# vps-r2_0-20-with-description.net
KiCad netlist of a schematic drawn in EAGLE
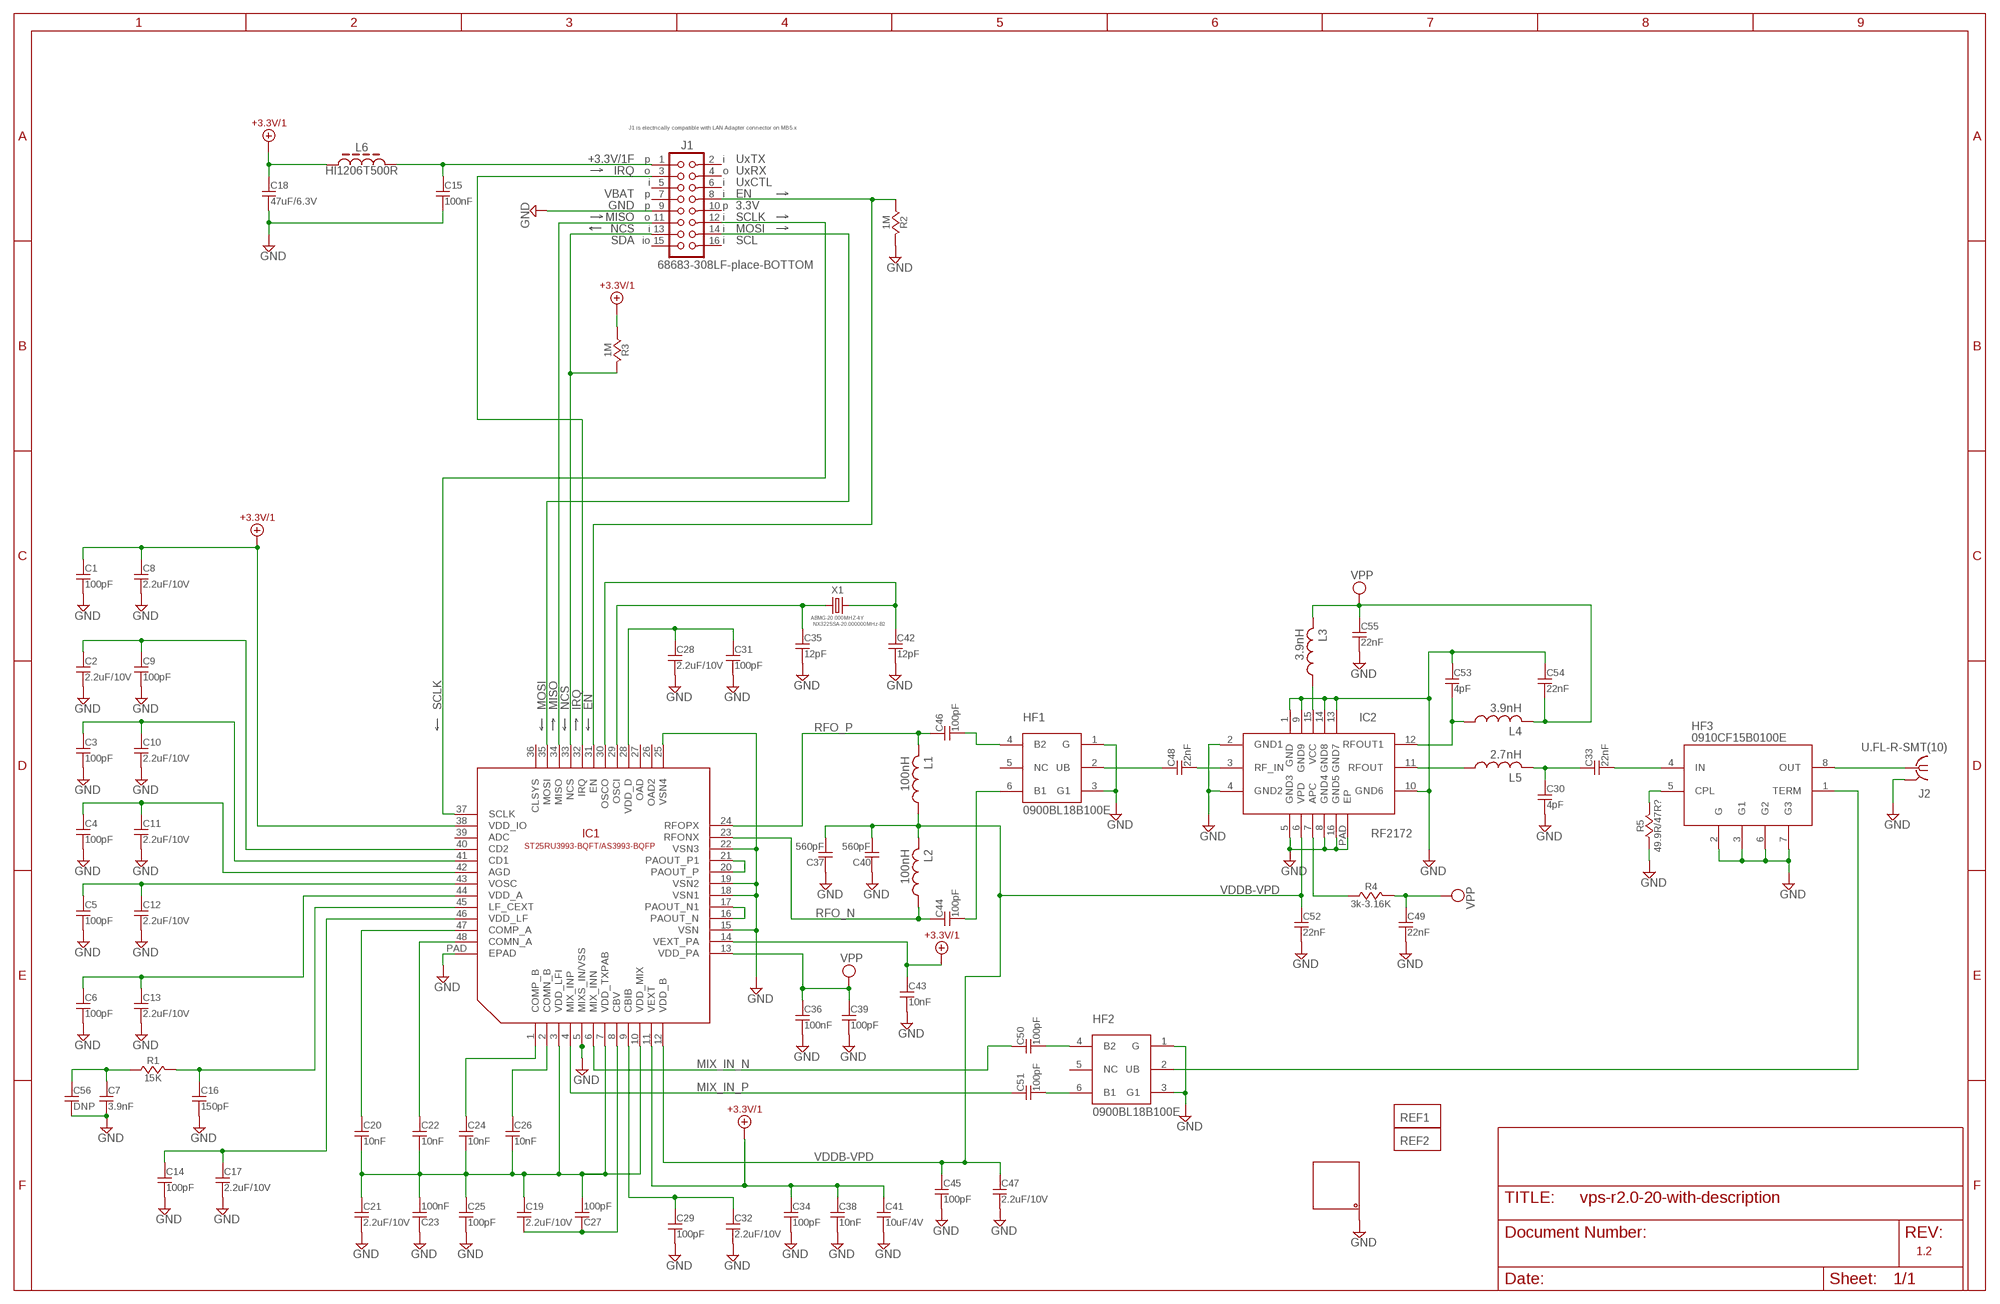
[diagram p0: schematic, sheet 1]

(export (version "E")
  (design (tool "Eeschema 10.0.6"))
  (components
    (comp (ref "C1")
      (value "100pF")
      (footprint "eagle-import:0603")
      (libsource (lib "eagle-import") (part "C-0603"))
    )
    (comp (ref "C2")
      (value "2.2uF/10V")
      (footprint "eagle-import:0603")
      (libsource (lib "eagle-import") (part "C-0603"))
    )
    (comp (ref "C3")
      (value "100pF")
      (footprint "eagle-import:0603")
      (libsource (lib "eagle-import") (part "C-0603"))
    )
    (comp (ref "C4")
      (value "100pF")
      (footprint "eagle-import:0603")
      (libsource (lib "eagle-import") (part "C-0603"))
    )
    (comp (ref "C5")
      (value "100pF")
      (footprint "eagle-import:0603")
      (libsource (lib "eagle-import") (part "C-0603"))
    )
    (comp (ref "C6")
      (value "100pF")
      (footprint "eagle-import:0603")
      (libsource (lib "eagle-import") (part "C-0603"))
    )
    (comp (ref "C7")
      (value "3.9nF")
      (footprint "eagle-import:0603")
      (libsource (lib "eagle-import") (part "C-0603"))
    )
    (comp (ref "C8")
      (value "2.2uF/10V")
      (footprint "eagle-import:0603")
      (libsource (lib "eagle-import") (part "C-0603"))
    )
    (comp (ref "C9")
      (value "100pF")
      (footprint "eagle-import:0603")
      (libsource (lib "eagle-import") (part "C-0603"))
    )
    (comp (ref "C10")
      (value "2.2uF/10V")
      (footprint "eagle-import:0603")
      (libsource (lib "eagle-import") (part "C-0603"))
    )
    (comp (ref "C11")
      (value "2.2uF/10V")
      (footprint "eagle-import:0603")
      (libsource (lib "eagle-import") (part "C-0603"))
    )
    (comp (ref "C12")
      (value "2.2uF/10V")
      (footprint "eagle-import:0603")
      (libsource (lib "eagle-import") (part "C-0603"))
    )
    (comp (ref "C13")
      (value "2.2uF/10V")
      (footprint "eagle-import:0603")
      (libsource (lib "eagle-import") (part "C-0603"))
    )
    (comp (ref "C14")
      (value "100pF")
      (footprint "eagle-import:0603")
      (libsource (lib "eagle-import") (part "C-0603"))
    )
    (comp (ref "C15")
      (value "100nF")
      (footprint "eagle-import:0603")
      (libsource (lib "eagle-import") (part "C-0603"))
    )
    (comp (ref "C16")
      (value "150pF")
      (footprint "eagle-import:0603")
      (libsource (lib "eagle-import") (part "C-0603"))
    )
    (comp (ref "C17")
      (value "2.2uF/10V")
      (footprint "eagle-import:0603")
      (libsource (lib "eagle-import") (part "C-0603"))
    )
    (comp (ref "C18")
      (value "47uF/6.3V")
      (footprint "eagle-import:1206")
      (libsource (lib "eagle-import") (part "C-1206"))
    )
    (comp (ref "C19")
      (value "2.2uF/10V")
      (footprint "eagle-import:0603")
      (libsource (lib "eagle-import") (part "C-0603"))
    )
    (comp (ref "C20")
      (value "10nF")
      (footprint "eagle-import:0603")
      (libsource (lib "eagle-import") (part "C-0603"))
    )
    (comp (ref "C21")
      (value "2.2uF/10V")
      (footprint "eagle-import:0603")
      (libsource (lib "eagle-import") (part "C-0603"))
    )
    (comp (ref "C22")
      (value "10nF")
      (footprint "eagle-import:0603")
      (libsource (lib "eagle-import") (part "C-0603"))
    )
    (comp (ref "C23")
      (value "100nF")
      (footprint "eagle-import:0603")
      (libsource (lib "eagle-import") (part "C-0603"))
    )
    (comp (ref "C24")
      (value "10nF")
      (footprint "eagle-import:0603")
      (libsource (lib "eagle-import") (part "C-0603"))
    )
    (comp (ref "C25")
      (value "100pF")
      (footprint "eagle-import:0603")
      (libsource (lib "eagle-import") (part "C-0603"))
    )
    (comp (ref "C26")
      (value "10nF")
      (footprint "eagle-import:0603")
      (libsource (lib "eagle-import") (part "C-0603"))
    )
    (comp (ref "C27")
      (value "100pF")
      (footprint "eagle-import:0603")
      (libsource (lib "eagle-import") (part "C-0603"))
    )
    (comp (ref "C28")
      (value "2.2uF/10V")
      (footprint "eagle-import:0603")
      (libsource (lib "eagle-import") (part "C-0603"))
    )
    (comp (ref "C29")
      (value "100pF")
      (footprint "eagle-import:0603")
      (libsource (lib "eagle-import") (part "C-0603"))
    )
    (comp (ref "C30")
      (value "4pF")
      (footprint "eagle-import:0603")
      (libsource (lib "eagle-import") (part "C-0603"))
    )
    (comp (ref "C31")
      (value "100pF")
      (footprint "eagle-import:0603")
      (libsource (lib "eagle-import") (part "C-0603"))
    )
    (comp (ref "C32")
      (value "2.2uF/10V")
      (footprint "eagle-import:0603")
      (libsource (lib "eagle-import") (part "C-0603"))
    )
    (comp (ref "C33")
      (value "22nF")
      (footprint "eagle-import:0603")
      (libsource (lib "eagle-import") (part "C-0603"))
    )
    (comp (ref "C34")
      (value "100pF")
      (footprint "eagle-import:0603")
      (libsource (lib "eagle-import") (part "C-0603"))
    )
    (comp (ref "C35")
      (value "12pF")
      (footprint "eagle-import:0603")
      (libsource (lib "eagle-import") (part "C-0603"))
    )
    (comp (ref "C36")
      (value "100nF")
      (footprint "eagle-import:0603")
      (libsource (lib "eagle-import") (part "C-0603"))
    )
    (comp (ref "C37")
      (value "560pF")
      (footprint "eagle-import:0603")
      (libsource (lib "eagle-import") (part "C-0603"))
    )
    (comp (ref "C38")
      (value "10nF")
      (footprint "eagle-import:0603")
      (libsource (lib "eagle-import") (part "C-0603"))
    )
    (comp (ref "C39")
      (value "100pF")
      (footprint "eagle-import:0603")
      (libsource (lib "eagle-import") (part "C-0603"))
    )
    (comp (ref "C40")
      (value "560pF")
      (footprint "eagle-import:0603")
      (libsource (lib "eagle-import") (part "C-0603"))
    )
    (comp (ref "C41")
      (value "10uF/4V")
      (footprint "eagle-import:0603")
      (libsource (lib "eagle-import") (part "C-0603"))
    )
    (comp (ref "C42")
      (value "12pF")
      (footprint "eagle-import:0603")
      (libsource (lib "eagle-import") (part "C-0603"))
    )
    (comp (ref "C43")
      (value "10nF")
      (footprint "eagle-import:0603")
      (libsource (lib "eagle-import") (part "C-0603"))
    )
    (comp (ref "C44")
      (value "100pF")
      (footprint "eagle-import:0603")
      (libsource (lib "eagle-import") (part "C-0603"))
    )
    (comp (ref "C45")
      (value "100pF")
      (footprint "eagle-import:0603")
      (libsource (lib "eagle-import") (part "C-0603"))
    )
    (comp (ref "C46")
      (value "100pF")
      (footprint "eagle-import:0603")
      (libsource (lib "eagle-import") (part "C-0603"))
    )
    (comp (ref "C47")
      (value "2.2uF/10V")
      (footprint "eagle-import:0603")
      (libsource (lib "eagle-import") (part "C-0603"))
    )
    (comp (ref "C48")
      (value "22nF")
      (footprint "eagle-import:0603")
      (libsource (lib "eagle-import") (part "C-0603"))
    )
    (comp (ref "C49")
      (value "22nF")
      (footprint "eagle-import:0603")
      (libsource (lib "eagle-import") (part "C-0603"))
    )
    (comp (ref "C50")
      (value "100pF")
      (footprint "eagle-import:0603")
      (libsource (lib "eagle-import") (part "C-0603"))
    )
    (comp (ref "C51")
      (value "100pF")
      (footprint "eagle-import:0603")
      (libsource (lib "eagle-import") (part "C-0603"))
    )
    (comp (ref "C52")
      (value "22nF")
      (footprint "eagle-import:0603")
      (libsource (lib "eagle-import") (part "C-0603"))
    )
    (comp (ref "C53")
      (value "4pF")
      (footprint "eagle-import:0603")
      (libsource (lib "eagle-import") (part "C-0603"))
    )
    (comp (ref "C54")
      (value "22nF")
      (footprint "eagle-import:0603")
      (libsource (lib "eagle-import") (part "C-0603"))
    )
    (comp (ref "C55")
      (value "22nF")
      (footprint "eagle-import:0603")
      (libsource (lib "eagle-import") (part "C-0603"))
    )
    (comp (ref "C56")
      (value "DNP")
      (footprint "eagle-import:0603")
      (libsource (lib "eagle-import") (part "C-0603"))
    )
    (comp (ref "HF1")
      (value "0900BL18B100E")
      (footprint "eagle-import:JTIBALUN")
      (fields (field (name "MF") "JOHANSON TECHNOLIGIES"))
      (libsource (lib "eagle-import") (part "JTI_BALUN"))
    )
    (comp (ref "HF2")
      (value "0900BL18B100E")
      (footprint "eagle-import:JTIBALUN")
      (fields (field (name "MF") "JOHANSON TECHNOLIGIES"))
      (libsource (lib "eagle-import") (part "JTI_BALUN"))
    )
    (comp (ref "HF3")
      (value "0910CF15B0100E")
      (footprint "eagle-import:JTICPL")
      (libsource (lib "eagle-import") (part "JTI_CLP_FIL"))
    )
    (comp (ref "IC1")
      (value "ST25RU3993-BQFT/AS3993-BQFP")
      (footprint "eagle-import:LFCSP_7X7_48")
      (libsource (lib "eagle-import") (part "AS3993-BQFP"))
    )
    (comp (ref "IC2")
      (value "RF2172")
      (footprint "eagle-import:QFN164X4")
      (libsource (lib "eagle-import") (part "RF2172"))
    )
    (comp (ref "J1")
      (value "68683-308LF-place-BOTTOM")
      (footprint "eagle-import:MA08-2")
      (libsource (lib "eagle-import") (part "MA08-2"))
    )
    (comp (ref "J2")
      (value "U.FL-R-SMT(10)")
      (footprint "eagle-import:MC-921")
      (libsource (lib "eagle-import") (part "MC-921"))
    )
    (comp (ref "L1")
      (value "100nH")
      (footprint "eagle-import:L0603")
      (libsource (lib "eagle-import") (part "L0603"))
    )
    (comp (ref "L2")
      (value "100nH")
      (footprint "eagle-import:L0603")
      (libsource (lib "eagle-import") (part "L0603"))
    )
    (comp (ref "L3")
      (value "3.9nH")
      (footprint "eagle-import:L0603")
      (libsource (lib "eagle-import") (part "L0603"))
    )
    (comp (ref "L4")
      (value "3.9nH")
      (footprint "eagle-import:L0603")
      (libsource (lib "eagle-import") (part "L0603"))
    )
    (comp (ref "L5")
      (value "2.7nH")
      (footprint "eagle-import:L0603")
      (libsource (lib "eagle-import") (part "L0603"))
    )
    (comp (ref "L6")
      (value "HI1206T500R")
      (footprint "eagle-import:1206")
      (libsource (lib "eagle-import") (part "L-1206"))
    )
    (comp (ref "PCB1")
      (value "PCB-VPS-1")
      (footprint "eagle-import:PCB-VPS")
      (libsource (lib "eagle-import") (part "PCB-VPS-1"))
    )
    (comp (ref "R1")
      (value "15K")
      (footprint "eagle-import:0603")
      (libsource (lib "eagle-import") (part "R-0603"))
    )
    (comp (ref "R2")
      (value "1M")
      (footprint "eagle-import:0603")
      (libsource (lib "eagle-import") (part "R-0603"))
    )
    (comp (ref "R3")
      (value "1M")
      (footprint "eagle-import:0603")
      (libsource (lib "eagle-import") (part "R-0603"))
    )
    (comp (ref "R4")
      (value "3k-3.16K")
      (footprint "eagle-import:0603")
      (libsource (lib "eagle-import") (part "R-0603"))
    )
    (comp (ref "R5")
      (value "49.9R/47R?")
      (footprint "eagle-import:0603")
      (libsource (lib "eagle-import") (part "R-0603"))
    )
    (comp (ref "REF1")
      (value "REF")
      (footprint "eagle-import:REF")
      (libsource (lib "eagle-import") (part "REF"))
    )
    (comp (ref "REF2")
      (value "REF")
      (footprint "eagle-import:REF")
      (libsource (lib "eagle-import") (part "REF"))
    )
    (comp (ref "X1")
      (value "ABMG-20.000MHZ-4Y")
      (footprint "eagle-import:7M")
      (libsource (lib "eagle-import") (part "XTAL-7M"))
    )
  )
  (nets
    (net (code "1") (name "+3.3V{slash}1") (class "Default")
      (node (ref "C1") (pin "1") (pinfunction "1_1") (pintype "passive"))
      (node (ref "C18") (pin "1") (pinfunction "1_1") (pintype "passive"))
      (node (ref "C34") (pin "1") (pinfunction "1_1") (pintype "passive"))
      (node (ref "C38") (pin "1") (pinfunction "1_1") (pintype "passive"))
      (node (ref "C41") (pin "1") (pinfunction "1_1") (pintype "passive"))
      (node (ref "C43") (pin "1") (pinfunction "1_1") (pintype "passive"))
      (node (ref "C8") (pin "1") (pinfunction "1_1") (pintype "passive"))
      (node (ref "IC1") (pin "11") (pinfunction "VEXT_11") (pintype "bidirectional"))
      (node (ref "IC1") (pin "14") (pinfunction "VEXT_PA_14") (pintype "bidirectional"))
      (node (ref "IC1") (pin "38") (pinfunction "VDD_IO_38") (pintype "bidirectional"))
      (node (ref "L6") (pin "1") (pinfunction "1_1") (pintype "passive"))
      (node (ref "R3") (pin "1") (pinfunction "1_1") (pintype "passive"))
    )
    (net (code "2") (name "/+3.3V{slash}1F") (class "Default")
      (node (ref "C15") (pin "1") (pinfunction "1_1") (pintype "passive"))
      (node (ref "J1") (pin "1") (pinfunction "1_1") (pintype "passive"))
      (node (ref "L6") (pin "2") (pinfunction "2_2") (pintype "passive"))
    )
    (net (code "3") (name "/EN") (class "Default")
      (node (ref "IC1") (pin "31") (pinfunction "EN_31") (pintype "bidirectional"))
      (node (ref "J1") (pin "8") (pinfunction "8_8") (pintype "passive"))
      (node (ref "R2") (pin "1") (pinfunction "1_1") (pintype "passive"))
    )
    (net (code "4") (name "/IRQ") (class "Default")
      (node (ref "IC1") (pin "32") (pinfunction "IRQ_32") (pintype "bidirectional"))
      (node (ref "J1") (pin "3") (pinfunction "3_3") (pintype "passive"))
    )
    (net (code "5") (name "/MISO") (class "Default")
      (node (ref "IC1") (pin "34") (pinfunction "MISO_34") (pintype "bidirectional"))
      (node (ref "J1") (pin "11") (pinfunction "11_11") (pintype "passive"))
    )
    (net (code "6") (name "/MIX_IN_N") (class "Default")
      (node (ref "C50") (pin "1") (pinfunction "1_1") (pintype "passive"))
      (node (ref "IC1") (pin "6") (pinfunction "MIX_INN_6") (pintype "bidirectional"))
    )
    (net (code "7") (name "/MIX_IN_P") (class "Default")
      (node (ref "C51") (pin "1") (pinfunction "1_1") (pintype "passive"))
      (node (ref "IC1") (pin "4") (pinfunction "MIX_INP_4") (pintype "bidirectional"))
    )
    (net (code "8") (name "/MOSI") (class "Default")
      (node (ref "IC1") (pin "35") (pinfunction "MOSI_35") (pintype "bidirectional"))
      (node (ref "J1") (pin "14") (pinfunction "14_14") (pintype "passive"))
    )
    (net (code "9") (name "/NCS") (class "Default")
      (node (ref "IC1") (pin "33") (pinfunction "NCS_33") (pintype "bidirectional"))
      (node (ref "J1") (pin "13") (pinfunction "13_13") (pintype "passive"))
      (node (ref "R3") (pin "2") (pinfunction "2_2") (pintype "passive"))
    )
    (net (code "10") (name "/RFO_N") (class "Default")
      (node (ref "C44") (pin "1") (pinfunction "1_1") (pintype "passive"))
      (node (ref "IC1") (pin "23") (pinfunction "RFONX_23") (pintype "bidirectional"))
      (node (ref "L2") (pin "1") (pinfunction "1_1") (pintype "passive"))
    )
    (net (code "11") (name "/RFO_P") (class "Default")
      (node (ref "C46") (pin "1") (pinfunction "1_1") (pintype "passive"))
      (node (ref "IC1") (pin "24") (pinfunction "RFOPX_24") (pintype "bidirectional"))
      (node (ref "L1") (pin "2") (pinfunction "2_2") (pintype "passive"))
    )
    (net (code "12") (name "/SCLK") (class "Default")
      (node (ref "IC1") (pin "37") (pinfunction "SCLK_37") (pintype "bidirectional"))
      (node (ref "J1") (pin "12") (pinfunction "12_12") (pintype "passive"))
    )
    (net (code "13") (name "/VDDB-VPD") (class "Default")
      (node (ref "C37") (pin "2") (pinfunction "2_2") (pintype "passive"))
      (node (ref "C40") (pin "2") (pinfunction "2_2") (pintype "passive"))
      (node (ref "C45") (pin "1") (pinfunction "1_1") (pintype "passive"))
      (node (ref "C47") (pin "1") (pinfunction "1_1") (pintype "passive"))
      (node (ref "C52") (pin "1") (pinfunction "1_1") (pintype "passive"))
      (node (ref "IC1") (pin "12") (pinfunction "VDD_B_12") (pintype "bidirectional"))
      (node (ref "IC2") (pin "6") (pinfunction "VPD_6") (pintype "bidirectional"))
      (node (ref "L1") (pin "1") (pinfunction "1_1") (pintype "passive"))
      (node (ref "L2") (pin "2") (pinfunction "2_2") (pintype "passive"))
    )
    (net (code "14") (name "GND") (class "Default")
      (node (ref "C1") (pin "2") (pinfunction "2_2") (pintype "passive"))
      (node (ref "C10") (pin "2") (pinfunction "2_2") (pintype "passive"))
      (node (ref "C11") (pin "2") (pinfunction "2_2") (pintype "passive"))
      (node (ref "C12") (pin "2") (pinfunction "2_2") (pintype "passive"))
      (node (ref "C13") (pin "2") (pinfunction "2_2") (pintype "passive"))
      (node (ref "C14") (pin "2") (pinfunction "2_2") (pintype "passive"))
      (node (ref "C15") (pin "2") (pinfunction "2_2") (pintype "passive"))
      (node (ref "C16") (pin "2") (pinfunction "2_2") (pintype "passive"))
      (node (ref "C17") (pin "2") (pinfunction "2_2") (pintype "passive"))
      (node (ref "C18") (pin "2") (pinfunction "2_2") (pintype "passive"))
      (node (ref "C2") (pin "2") (pinfunction "2_2") (pintype "passive"))
      (node (ref "C21") (pin "2") (pinfunction "2_2") (pintype "passive"))
      (node (ref "C23") (pin "1") (pinfunction "1_1") (pintype "passive"))
      (node (ref "C25") (pin "2") (pinfunction "2_2") (pintype "passive"))
      (node (ref "C28") (pin "2") (pinfunction "2_2") (pintype "passive"))
      (node (ref "C29") (pin "2") (pinfunction "2_2") (pintype "passive"))
      (node (ref "C3") (pin "2") (pinfunction "2_2") (pintype "passive"))
      (node (ref "C30") (pin "2") (pinfunction "2_2") (pintype "passive"))
      (node (ref "C31") (pin "2") (pinfunction "2_2") (pintype "passive"))
      (node (ref "C32") (pin "2") (pinfunction "2_2") (pintype "passive"))
      (node (ref "C34") (pin "2") (pinfunction "2_2") (pintype "passive"))
      (node (ref "C35") (pin "2") (pinfunction "2_2") (pintype "passive"))
      (node (ref "C36") (pin "2") (pinfunction "2_2") (pintype "passive"))
      (node (ref "C37") (pin "1") (pinfunction "1_1") (pintype "passive"))
      (node (ref "C38") (pin "2") (pinfunction "2_2") (pintype "passive"))
      (node (ref "C39") (pin "2") (pinfunction "2_2") (pintype "passive"))
      (node (ref "C4") (pin "2") (pinfunction "2_2") (pintype "passive"))
      (node (ref "C40") (pin "1") (pinfunction "1_1") (pintype "passive"))
      (node (ref "C41") (pin "2") (pinfunction "2_2") (pintype "passive"))
      (node (ref "C42") (pin "2") (pinfunction "2_2") (pintype "passive"))
      (node (ref "C43") (pin "2") (pinfunction "2_2") (pintype "passive"))
      (node (ref "C45") (pin "2") (pinfunction "2_2") (pintype "passive"))
      (node (ref "C47") (pin "2") (pinfunction "2_2") (pintype "passive"))
      (node (ref "C49") (pin "2") (pinfunction "2_2") (pintype "passive"))
      (node (ref "C5") (pin "2") (pinfunction "2_2") (pintype "passive"))
      (node (ref "C52") (pin "2") (pinfunction "2_2") (pintype "passive"))
      (node (ref "C53") (pin "1") (pinfunction "1_1") (pintype "passive"))
      (node (ref "C54") (pin "1") (pinfunction "1_1") (pintype "passive"))
      (node (ref "C55") (pin "2") (pinfunction "2_2") (pintype "passive"))
      (node (ref "C56") (pin "2") (pinfunction "2_2") (pintype "passive"))
      (node (ref "C6") (pin "2") (pinfunction "2_2") (pintype "passive"))
      (node (ref "C7") (pin "2") (pinfunction "2_2") (pintype "passive"))
      (node (ref "C8") (pin "2") (pinfunction "2_2") (pintype "passive"))
      (node (ref "C9") (pin "2") (pinfunction "2_2") (pintype "passive"))
      (node (ref "HF1") (pin "1") (pinfunction "G_1") (pintype "bidirectional"))
      (node (ref "HF1") (pin "3") (pinfunction "G1_3") (pintype "bidirectional"))
      (node (ref "HF2") (pin "1") (pinfunction "G_1") (pintype "bidirectional"))
      (node (ref "HF2") (pin "3") (pinfunction "G1_3") (pintype "bidirectional"))
      (node (ref "HF3") (pin "2") (pinfunction "G_2") (pintype "bidirectional"))
      (node (ref "HF3") (pin "3") (pinfunction "G1_3") (pintype "bidirectional"))
      (node (ref "HF3") (pin "6") (pinfunction "G2_6") (pintype "bidirectional"))
      (node (ref "HF3") (pin "7") (pinfunction "G3_7") (pintype "bidirectional"))
      (node (ref "IC1") (pin "15") (pinfunction "VSN_15") (pintype "bidirectional"))
      (node (ref "IC1") (pin "18") (pinfunction "VSN1_18") (pintype "bidirectional"))
      (node (ref "IC1") (pin "19") (pinfunction "VSN2_19") (pintype "bidirectional"))
      (node (ref "IC1") (pin "22") (pinfunction "VSN3_22") (pintype "bidirectional"))
      (node (ref "IC1") (pin "25") (pinfunction "VSN4_25") (pintype "bidirectional"))
      (node (ref "IC1") (pin "5") (pinfunction "MIXS_IN/VSS_5") (pintype "bidirectional"))
      (node (ref "IC1") (pin "PAD") (pinfunction "EPAD_PAD") (pintype "bidirectional"))
      (node (ref "IC2") (pin "1") (pinfunction "GND_1") (pintype "bidirectional"))
      (node (ref "IC2") (pin "10") (pinfunction "GND6_10") (pintype "bidirectional"))
      (node (ref "IC2") (pin "13") (pinfunction "GND7_13") (pintype "bidirectional"))
      (node (ref "IC2") (pin "14") (pinfunction "GND8_14") (pintype "bidirectional"))
      (node (ref "IC2") (pin "16") (pinfunction "GND5_16") (pintype "bidirectional"))
      (node (ref "IC2") (pin "2") (pinfunction "GND1_2") (pintype "bidirectional"))
      (node (ref "IC2") (pin "4") (pinfunction "GND2_4") (pintype "bidirectional"))
      (node (ref "IC2") (pin "5") (pinfunction "GND3_5") (pintype "bidirectional"))
      (node (ref "IC2") (pin "8") (pinfunction "GND4_8") (pintype "bidirectional"))
      (node (ref "IC2") (pin "9") (pinfunction "GND9_9") (pintype "bidirectional"))
      (node (ref "IC2") (pin "PAD") (pinfunction "EP_PAD") (pintype "bidirectional"))
      (node (ref "J1") (pin "9") (pinfunction "9_9") (pintype "passive"))
      (node (ref "J2") (pin "2@1") (pinfunction "GND_2@1") (pintype "passive"))
      (node (ref "J2") (pin "2@2") (pinfunction "GND_2@2") (pintype "passive"))
      (node (ref "PCB1") (pin "VPS_PCB_1") (pinfunction "VPS_PCB_1_VPS_PCB_1") (pintype "bidirectional"))
      (node (ref "R2") (pin "2") (pinfunction "2_2") (pintype "passive"))
      (node (ref "R5") (pin "1") (pinfunction "1_1") (pintype "passive"))
    )
    (net (code "15") (name "Net-(C30-Pad1)") (class "Default")
      (node (ref "C30") (pin "1") (pinfunction "1_1") (pintype "passive"))
      (node (ref "C33") (pin "1") (pinfunction "1_1") (pintype "passive"))
      (node (ref "L5") (pin "2") (pinfunction "2_2") (pintype "passive"))
    )
    (net (code "16") (name "Net-(C56-Pad1)") (class "Default")
      (node (ref "C56") (pin "1") (pinfunction "1_1") (pintype "passive"))
      (node (ref "C7") (pin "1") (pinfunction "1_1") (pintype "passive"))
      (node (ref "R1") (pin "1") (pinfunction "1_1") (pintype "passive"))
    )
    (net (code "17") (name "Net-(HF1-B1)") (class "Default")
      (node (ref "C44") (pin "2") (pinfunction "2_2") (pintype "passive"))
      (node (ref "HF1") (pin "6") (pinfunction "B1_6") (pintype "bidirectional"))
    )
    (net (code "18") (name "Net-(HF1-B2)") (class "Default")
      (node (ref "C46") (pin "2") (pinfunction "2_2") (pintype "passive"))
      (node (ref "HF1") (pin "4") (pinfunction "B2_4") (pintype "bidirectional"))
    )
    (net (code "19") (name "Net-(HF1-UB)") (class "Default")
      (node (ref "C48") (pin "1") (pinfunction "1_1") (pintype "passive"))
      (node (ref "HF1") (pin "2") (pinfunction "UB_2") (pintype "bidirectional"))
    )
    (net (code "20") (name "Net-(HF2-B1)") (class "Default")
      (node (ref "C51") (pin "2") (pinfunction "2_2") (pintype "passive"))
      (node (ref "HF2") (pin "6") (pinfunction "B1_6") (pintype "bidirectional"))
    )
    (net (code "21") (name "Net-(HF2-B2)") (class "Default")
      (node (ref "C50") (pin "2") (pinfunction "2_2") (pintype "passive"))
      (node (ref "HF2") (pin "4") (pinfunction "B2_4") (pintype "bidirectional"))
    )
    (net (code "22") (name "Net-(HF2-UB)") (class "Default")
      (node (ref "HF2") (pin "2") (pinfunction "UB_2") (pintype "bidirectional"))
      (node (ref "HF3") (pin "1") (pinfunction "TERM_1") (pintype "bidirectional"))
    )
    (net (code "23") (name "Net-(HF3-CPL)") (class "Default")
      (node (ref "HF3") (pin "5") (pinfunction "CPL_5") (pintype "bidirectional"))
      (node (ref "R5") (pin "2") (pinfunction "2_2") (pintype "passive"))
    )
    (net (code "24") (name "Net-(HF3-IN)") (class "Default")
      (node (ref "C33") (pin "2") (pinfunction "2_2") (pintype "passive"))
      (node (ref "HF3") (pin "4") (pinfunction "IN_4") (pintype "bidirectional"))
    )
    (net (code "25") (name "Net-(HF3-OUT)") (class "Default")
      (node (ref "HF3") (pin "8") (pinfunction "OUT_8") (pintype "bidirectional"))
      (node (ref "J2") (pin "1") (pinfunction "1_1") (pintype "passive"))
    )
    (net (code "26") (name "Net-(IC1-AGD)") (class "Default")
      (node (ref "C11") (pin "1") (pinfunction "1_1") (pintype "passive"))
      (node (ref "C4") (pin "1") (pinfunction "1_1") (pintype "passive"))
      (node (ref "IC1") (pin "42") (pinfunction "AGD_42") (pintype "bidirectional"))
    )
    (net (code "27") (name "Net-(IC1-CBIB)") (class "Default")
      (node (ref "C29") (pin "1") (pinfunction "1_1") (pintype "passive"))
      (node (ref "C32") (pin "1") (pinfunction "1_1") (pintype "passive"))
      (node (ref "IC1") (pin "9") (pinfunction "CBIB_9") (pintype "bidirectional"))
    )
    (net (code "28") (name "Net-(IC1-CBV)") (class "Default")
      (node (ref "C19") (pin "2") (pinfunction "2_2") (pintype "passive"))
      (node (ref "C27") (pin "1") (pinfunction "1_1") (pintype "passive"))
      (node (ref "IC1") (pin "8") (pinfunction "CBV_8") (pintype "bidirectional"))
    )
    (net (code "29") (name "Net-(IC1-CD1)") (class "Default")
      (node (ref "C10") (pin "1") (pinfunction "1_1") (pintype "passive"))
      (node (ref "C3") (pin "1") (pinfunction "1_1") (pintype "passive"))
      (node (ref "IC1") (pin "41") (pinfunction "CD1_41") (pintype "bidirectional"))
    )
    (net (code "30") (name "Net-(IC1-CD2)") (class "Default")
      (node (ref "C2") (pin "1") (pinfunction "1_1") (pintype "passive"))
      (node (ref "C9") (pin "1") (pinfunction "1_1") (pintype "passive"))
      (node (ref "IC1") (pin "40") (pinfunction "CD2_40") (pintype "bidirectional"))
    )
    (net (code "31") (name "Net-(IC1-COMN_A)") (class "Default")
      (node (ref "C22") (pin "1") (pinfunction "1_1") (pintype "passive"))
      (node (ref "IC1") (pin "48") (pinfunction "COMN_A_48") (pintype "bidirectional"))
    )
    (net (code "32") (name "Net-(IC1-COMN_B)") (class "Default")
      (node (ref "C26") (pin "1") (pinfunction "1_1") (pintype "passive"))
      (node (ref "IC1") (pin "2") (pinfunction "COMN_B_2") (pintype "bidirectional"))
    )
    (net (code "33") (name "Net-(IC1-COMP_A)") (class "Default")
      (node (ref "C20") (pin "1") (pinfunction "1_1") (pintype "passive"))
      (node (ref "IC1") (pin "47") (pinfunction "COMP_A_47") (pintype "bidirectional"))
    )
    (net (code "34") (name "Net-(IC1-COMP_B)") (class "Default")
      (node (ref "C24") (pin "1") (pinfunction "1_1") (pintype "passive"))
      (node (ref "IC1") (pin "1") (pinfunction "COMP_B_1") (pintype "bidirectional"))
    )
    (net (code "35") (name "Net-(IC1-LF_CEXT)") (class "Default")
      (node (ref "C16") (pin "1") (pinfunction "1_1") (pintype "passive"))
      (node (ref "IC1") (pin "45") (pinfunction "LF_CEXT_45") (pintype "bidirectional"))
      (node (ref "R1") (pin "2") (pinfunction "2_2") (pintype "passive"))
    )
    (net (code "36") (name "Net-(IC1-OSCI)") (class "Default")
      (node (ref "C35") (pin "1") (pinfunction "1_1") (pintype "passive"))
      (node (ref "IC1") (pin "29") (pinfunction "OSCI_29") (pintype "bidirectional"))
      (node (ref "X1") (pin "1") (pinfunction "1_1") (pintype "passive"))
    )
    (net (code "37") (name "Net-(IC1-OSCO)") (class "Default")
      (node (ref "C42") (pin "1") (pinfunction "1_1") (pintype "passive"))
      (node (ref "IC1") (pin "30") (pinfunction "OSCO_30") (pintype "bidirectional"))
      (node (ref "X1") (pin "3") (pinfunction "2_3") (pintype "passive"))
    )
    (net (code "38") (name "Net-(IC1-PAOUT_N)") (class "Default")
      (node (ref "IC1") (pin "16") (pinfunction "PAOUT_N_16") (pintype "bidirectional"))
      (node (ref "IC1") (pin "17") (pinfunction "PAOUT_N1_17") (pintype "bidirectional"))
    )
    (net (code "39") (name "Net-(IC1-PAOUT_P)") (class "Default")
      (node (ref "IC1") (pin "20") (pinfunction "PAOUT_P_20") (pintype "bidirectional"))
      (node (ref "IC1") (pin "21") (pinfunction "PAOUT_P1_21") (pintype "bidirectional"))
    )
    (net (code "40") (name "Net-(IC1-VDD_A)") (class "Default")
      (node (ref "C13") (pin "1") (pinfunction "1_1") (pintype "passive"))
      (node (ref "C6") (pin "1") (pinfunction "1_1") (pintype "passive"))
      (node (ref "IC1") (pin "44") (pinfunction "VDD_A_44") (pintype "bidirectional"))
    )
    (net (code "41") (name "Net-(IC1-VDD_D)") (class "Default")
      (node (ref "C28") (pin "1") (pinfunction "1_1") (pintype "passive"))
      (node (ref "C31") (pin "1") (pinfunction "1_1") (pintype "passive"))
      (node (ref "IC1") (pin "28") (pinfunction "VDD_D_28") (pintype "bidirectional"))
    )
    (net (code "42") (name "Net-(IC1-VDD_LF)") (class "Default")
      (node (ref "C14") (pin "1") (pinfunction "1_1") (pintype "passive"))
      (node (ref "C17") (pin "1") (pinfunction "1_1") (pintype "passive"))
      (node (ref "IC1") (pin "46") (pinfunction "VDD_LF_46") (pintype "bidirectional"))
    )
    (net (code "43") (name "Net-(IC1-VDD_LFI)") (class "Default")
      (node (ref "C19") (pin "1") (pinfunction "1_1") (pintype "passive"))
      (node (ref "C20") (pin "2") (pinfunction "2_2") (pintype "passive"))
      (node (ref "C21") (pin "1") (pinfunction "1_1") (pintype "passive"))
      (node (ref "C22") (pin "2") (pinfunction "2_2") (pintype "passive"))
      (node (ref "C23") (pin "2") (pinfunction "2_2") (pintype "passive"))
      (node (ref "C24") (pin "2") (pinfunction "2_2") (pintype "passive"))
      (node (ref "C25") (pin "1") (pinfunction "1_1") (pintype "passive"))
      (node (ref "C26") (pin "2") (pinfunction "2_2") (pintype "passive"))
      (node (ref "C27") (pin "2") (pinfunction "2_2") (pintype "passive"))
      (node (ref "IC1") (pin "10") (pinfunction "VDD_MIX_10") (pintype "bidirectional"))
      (node (ref "IC1") (pin "3") (pinfunction "VDD_LFI_3") (pintype "bidirectional"))
      (node (ref "IC1") (pin "7") (pinfunction "VDD_TXPAB_7") (pintype "bidirectional"))
    )
    (net (code "44") (name "Net-(IC1-VOSC)") (class "Default")
      (node (ref "C12") (pin "1") (pinfunction "1_1") (pintype "passive"))
      (node (ref "C5") (pin "1") (pinfunction "1_1") (pintype "passive"))
      (node (ref "IC1") (pin "43") (pinfunction "VOSC_43") (pintype "bidirectional"))
    )
    (net (code "45") (name "Net-(IC2-APC)") (class "Default")
      (node (ref "IC2") (pin "7") (pinfunction "APC_7") (pintype "bidirectional"))
      (node (ref "R4") (pin "1") (pinfunction "1_1") (pintype "passive"))
    )
    (net (code "46") (name "Net-(IC2-RFOUT)") (class "Default")
      (node (ref "IC2") (pin "11") (pinfunction "RFOUT_11") (pintype "bidirectional"))
      (node (ref "L5") (pin "1") (pinfunction "1_1") (pintype "passive"))
    )
    (net (code "47") (name "Net-(IC2-RFOUT1)") (class "Default")
      (node (ref "C53") (pin "2") (pinfunction "2_2") (pintype "passive"))
      (node (ref "IC2") (pin "12") (pinfunction "RFOUT1_12") (pintype "bidirectional"))
      (node (ref "L4") (pin "1") (pinfunction "1_1") (pintype "passive"))
    )
    (net (code "48") (name "Net-(IC2-RF_IN)") (class "Default")
      (node (ref "C48") (pin "2") (pinfunction "2_2") (pintype "passive"))
      (node (ref "IC2") (pin "3") (pinfunction "RF_IN_3") (pintype "bidirectional"))
    )
    (net (code "49") (name "Net-(IC2-VCC)") (class "Default")
      (node (ref "IC2") (pin "15") (pinfunction "VCC_15") (pintype "bidirectional"))
      (node (ref "L3") (pin "1") (pinfunction "1_1") (pintype "passive"))
    )
    (net (code "50") (name "VPP") (class "Default")
      (node (ref "C36") (pin "1") (pinfunction "1_1") (pintype "passive"))
      (node (ref "C39") (pin "1") (pinfunction "1_1") (pintype "passive"))
      (node (ref "C49") (pin "1") (pinfunction "1_1") (pintype "passive"))
      (node (ref "C54") (pin "2") (pinfunction "2_2") (pintype "passive"))
      (node (ref "C55") (pin "1") (pinfunction "1_1") (pintype "passive"))
      (node (ref "IC1") (pin "13") (pinfunction "VDD_PA_13") (pintype "bidirectional"))
      (node (ref "L3") (pin "2") (pinfunction "2_2") (pintype "passive"))
      (node (ref "L4") (pin "2") (pinfunction "2_2") (pintype "passive"))
      (node (ref "R4") (pin "2") (pinfunction "2_2") (pintype "passive"))
    )
    (net (code "51") (name "unconnected-(HF1-NC-Pad5)") (class "Default")
      (node (ref "HF1") (pin "5") (pinfunction "NC_5") (pintype "bidirectional"))
    )
    (net (code "52") (name "unconnected-(HF2-NC-Pad5)") (class "Default")
      (node (ref "HF2") (pin "5") (pinfunction "NC_5") (pintype "bidirectional"))
    )
    (net (code "53") (name "unconnected-(IC1-ADC-Pad39)") (class "Default")
      (node (ref "IC1") (pin "39") (pinfunction "ADC_39") (pintype "bidirectional"))
    )
    (net (code "54") (name "unconnected-(IC1-CLSYS-Pad36)") (class "Default")
      (node (ref "IC1") (pin "36") (pinfunction "CLSYS_36") (pintype "bidirectional"))
    )
    (net (code "55") (name "unconnected-(IC1-OAD-Pad27)") (class "Default")
      (node (ref "IC1") (pin "27") (pinfunction "OAD_27") (pintype "bidirectional"))
    )
    (net (code "56") (name "unconnected-(IC1-OAD2-Pad26)") (class "Default")
      (node (ref "IC1") (pin "26") (pinfunction "OAD2_26") (pintype "bidirectional"))
    )
    (net (code "57") (name "unconnected-(J1-Pad2)") (class "Default")
      (node (ref "J1") (pin "2") (pinfunction "2_2") (pintype "passive"))
    )
    (net (code "58") (name "unconnected-(J1-Pad4)") (class "Default")
      (node (ref "J1") (pin "4") (pinfunction "4_4") (pintype "passive"))
    )
    (net (code "59") (name "unconnected-(J1-Pad5)") (class "Default")
      (node (ref "J1") (pin "5") (pinfunction "5_5") (pintype "passive"))
    )
    (net (code "60") (name "unconnected-(J1-Pad6)") (class "Default")
      (node (ref "J1") (pin "6") (pinfunction "6_6") (pintype "passive"))
    )
    (net (code "61") (name "unconnected-(J1-Pad7)") (class "Default")
      (node (ref "J1") (pin "7") (pinfunction "7_7") (pintype "passive"))
    )
    (net (code "62") (name "unconnected-(J1-Pad10)") (class "Default")
      (node (ref "J1") (pin "10") (pinfunction "10_10") (pintype "passive"))
    )
    (net (code "63") (name "unconnected-(J1-Pad15)") (class "Default")
      (node (ref "J1") (pin "15") (pinfunction "15_15") (pintype "passive"))
    )
    (net (code "64") (name "unconnected-(J1-Pad16)") (class "Default")
      (node (ref "J1") (pin "16") (pinfunction "16_16") (pintype "passive"))
    )
  )
)
